# Board1.net
KiCad netlist of a schematic drawn in EAGLE
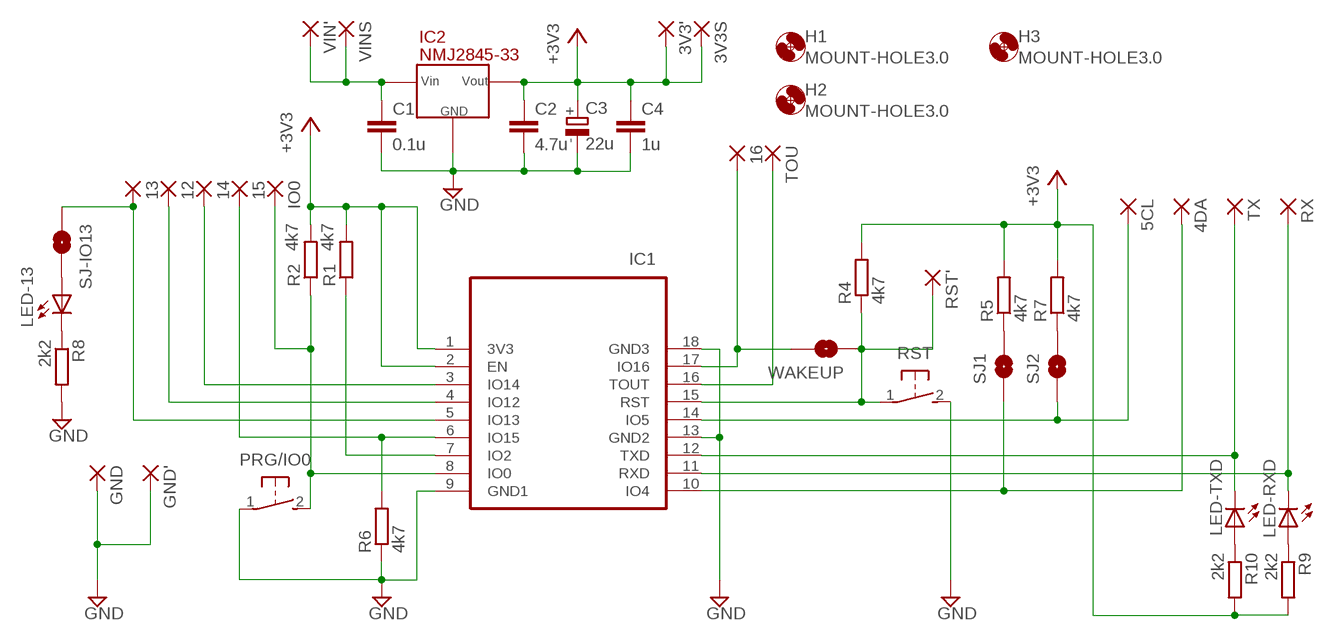
[diagram p0: schematic, sheet 1]

(export (version "E")
  (design (tool "Eeschema 10.0.6"))
  (components
    (comp (ref "3V3'")
      (value "1,6/0,8")
      (footprint "eagle-import:1,6_0,8")
      (libsource (lib "eagle-import") (part "1,6/0,8"))
    )
    (comp (ref "3V3S")
      (value "1,6/0,8")
      (footprint "eagle-import:1,6_0,8")
      (libsource (lib "eagle-import") (part "1,6/0,8"))
    )
    (comp (ref "4DA")
      (value "1,6/0,8")
      (footprint "eagle-import:1,6_0,8")
      (libsource (lib "eagle-import") (part "1,6/0,8"))
    )
    (comp (ref "5CL")
      (value "1,6/0,8")
      (footprint "eagle-import:1,6_0,8")
      (libsource (lib "eagle-import") (part "1,6/0,8"))
    )
    (comp (ref "12")
      (value "1,6/0,8")
      (footprint "eagle-import:1,6_0,8")
      (libsource (lib "eagle-import") (part "1,6/0,8"))
    )
    (comp (ref "13")
      (value "1,6/0,8")
      (footprint "eagle-import:1,6_0,8")
      (libsource (lib "eagle-import") (part "1,6/0,8"))
    )
    (comp (ref "14")
      (value "1,6/0,8")
      (footprint "eagle-import:1,6_0,8")
      (libsource (lib "eagle-import") (part "1,6/0,8"))
    )
    (comp (ref "15")
      (value "1,6/0,8")
      (footprint "eagle-import:1,6_0,8")
      (libsource (lib "eagle-import") (part "1,6/0,8"))
    )
    (comp (ref "16")
      (value "1,6/0,8")
      (footprint "eagle-import:1,6_0,8")
      (libsource (lib "eagle-import") (part "1,6/0,8"))
    )
    (comp (ref "C1")
      (value "0.1u")
      (footprint "eagle-import:C0603")
      (libsource (lib "eagle-import") (part "C-EUC0603"))
    )
    (comp (ref "C2")
      (value "4.7u")
      (footprint "eagle-import:C0805")
      (libsource (lib "eagle-import") (part "resistor_C-EUC0805"))
    )
    (comp (ref "C3")
      (value "22u")
      (footprint "eagle-import:C6")
      (libsource (lib "eagle-import") (part "OS-CON/C6C"))
    )
    (comp (ref "C4")
      (value "1u")
      (footprint "eagle-import:C0603")
      (libsource (lib "eagle-import") (part "C-EUC0603"))
    )
    (comp (ref "GND")
      (value "1,6/0,8")
      (footprint "eagle-import:1,6_0,8")
      (libsource (lib "eagle-import") (part "1,6/0,8"))
    )
    (comp (ref "GND'")
      (value "1,6/0,8")
      (footprint "eagle-import:1,6_0,8")
      (libsource (lib "eagle-import") (part "1,6/0,8"))
    )
    (comp (ref "H1")
      (value "MOUNT-HOLE3.0")
      (footprint "eagle-import:3,0")
      (libsource (lib "eagle-import") (part "MOUNT-HOLE3.0"))
    )
    (comp (ref "H2")
      (value "MOUNT-HOLE3.0")
      (footprint "eagle-import:3,0")
      (libsource (lib "eagle-import") (part "MOUNT-HOLE3.0"))
    )
    (comp (ref "H3")
      (value "MOUNT-HOLE3.0")
      (footprint "eagle-import:3,0")
      (libsource (lib "eagle-import") (part "MOUNT-HOLE3.0"))
    )
    (comp (ref "IC1")
      (value "ESP-WROOM-02FRONT-FACE")
      (footprint "eagle-import:FRONT-FACE")
      (libsource (lib "eagle-import") (part "ESP-WROOM-02FRONT-FACE"))
    )
    (comp (ref "IC2")
      (value "NMJ2845-33")
      (footprint "eagle-import:TO-252-3")
      (libsource (lib "eagle-import") (part "NJM2845DL1"))
    )
    (comp (ref "IO0")
      (value "1,6/0,8")
      (footprint "eagle-import:1,6_0,8")
      (libsource (lib "eagle-import") (part "1,6/0,8"))
    )
    (comp (ref "LED-13")
      (value "IO13")
      (footprint "eagle-import:CHIP-LED0603")
      (libsource (lib "eagle-import") (part "LEDCHIP-LED0603"))
    )
    (comp (ref "LED-RXD")
      (value "R")
      (footprint "eagle-import:CHIP-LED0603")
      (libsource (lib "eagle-import") (part "LEDCHIP-LED0603"))
    )
    (comp (ref "LED-TXD")
      (value "T")
      (footprint "eagle-import:CHIP-LED0603")
      (libsource (lib "eagle-import") (part "LEDCHIP-LED0603"))
    )
    (comp (ref "PRG/IO0")
      (value "SWITCH-TACTILESW")
      (footprint "eagle-import:SWITCH-TACTILE")
      (libsource (lib "eagle-import") (part "SWITCH-TACTILESW"))
    )
    (comp (ref "R1")
      (value "4k7")
      (footprint "eagle-import:R0603")
      (libsource (lib "eagle-import") (part "R-EU_R0603"))
    )
    (comp (ref "R2")
      (value "4k7")
      (footprint "eagle-import:R0603")
      (libsource (lib "eagle-import") (part "R-EU_R0603"))
    )
    (comp (ref "R4")
      (value "4k7")
      (footprint "eagle-import:R0603")
      (libsource (lib "eagle-import") (part "R-EU_R0603"))
    )
    (comp (ref "R5")
      (value "4k7")
      (footprint "eagle-import:R0603")
      (libsource (lib "eagle-import") (part "R-EU_R0603"))
    )
    (comp (ref "R6")
      (value "4k7")
      (footprint "eagle-import:R0603")
      (libsource (lib "eagle-import") (part "R-EU_R0603"))
    )
    (comp (ref "R7")
      (value "4k7")
      (footprint "eagle-import:R0603")
      (libsource (lib "eagle-import") (part "R-EU_R0603"))
    )
    (comp (ref "R8")
      (value "2k2")
      (footprint "eagle-import:R0603")
      (libsource (lib "eagle-import") (part "R-EU_R0603"))
    )
    (comp (ref "R9")
      (value "2k2")
      (footprint "eagle-import:R0603")
      (libsource (lib "eagle-import") (part "R-EU_R0603"))
    )
    (comp (ref "R10")
      (value "2k2")
      (footprint "eagle-import:R0603")
      (libsource (lib "eagle-import") (part "R-EU_R0603"))
    )
    (comp (ref "RST")
      (value "SWITCH-TACTILESW")
      (footprint "eagle-import:SWITCH-TACTILE")
      (libsource (lib "eagle-import") (part "SWITCH-TACTILESW"))
    )
    (comp (ref "RST'")
      (value "1,6/0,8")
      (footprint "eagle-import:1,6_0,8")
      (libsource (lib "eagle-import") (part "1,6/0,8"))
    )
    (comp (ref "RX")
      (value "1,6/0,8")
      (footprint "eagle-import:1,6_0,8")
      (libsource (lib "eagle-import") (part "1,6/0,8"))
    )
    (comp (ref "SJ-IO13")
      (value "SOLDERJUMPERNO")
      (footprint "eagle-import:SJ_2S-NO")
      (libsource (lib "eagle-import") (part "SOLDERJUMPERNO"))
    )
    (comp (ref "SJ1")
      (value "SDA/PU")
      (footprint "eagle-import:SJ_2S-NO")
      (libsource (lib "eagle-import") (part "SOLDERJUMPERNO"))
    )
    (comp (ref "SJ2")
      (value "SCL/PU")
      (footprint "eagle-import:SJ_2S-NO")
      (libsource (lib "eagle-import") (part "SOLDERJUMPERNO"))
    )
    (comp (ref "TOU")
      (value "1,6/0,8")
      (footprint "eagle-import:1,6_0,8")
      (libsource (lib "eagle-import") (part "1,6/0,8"))
    )
    (comp (ref "TX")
      (value "1,6/0,8")
      (footprint "eagle-import:1,6_0,8")
      (libsource (lib "eagle-import") (part "1,6/0,8"))
    )
    (comp (ref "VIN'")
      (value "1,6/0,8")
      (footprint "eagle-import:1,6_0,8")
      (libsource (lib "eagle-import") (part "1,6/0,8"))
    )
    (comp (ref "VINS")
      (value "1,6/0,8")
      (footprint "eagle-import:1,6_0,8")
      (libsource (lib "eagle-import") (part "1,6/0,8"))
    )
    (comp (ref "WAKEUP")
      (value "SOLDERJUMPERNO")
      (footprint "eagle-import:SJ_2S-NO")
      (libsource (lib "eagle-import") (part "SOLDERJUMPERNO"))
    )
  )
  (nets
    (net (code "1") (name "+3V3") (class "Default")
      (node (ref "3V3'") (pin "1") (pinfunction "P_1") (pintype "passive"))
      (node (ref "3V3S") (pin "1") (pinfunction "P_1") (pintype "passive"))
      (node (ref "C2") (pin "1") (pinfunction "1_1") (pintype "passive"))
      (node (ref "C3") (pin "+") (pinfunction "+_+") (pintype "passive"))
      (node (ref "C4") (pin "1") (pinfunction "1_1") (pintype "passive"))
      (node (ref "IC1") (pin "1") (pinfunction "3V3_1") (pintype "power_in"))
      (node (ref "IC1") (pin "2") (pinfunction "EN_2") (pintype "bidirectional"))
      (node (ref "IC2") (pin "VOUT") (pinfunction "VOUT_VOUT") (pintype "power_in"))
      (node (ref "R1") (pin "2") (pinfunction "2_2") (pintype "passive"))
      (node (ref "R10") (pin "2") (pinfunction "2_2") (pintype "passive"))
      (node (ref "R2") (pin "2") (pinfunction "2_2") (pintype "passive"))
      (node (ref "R4") (pin "2") (pinfunction "2_2") (pintype "passive"))
      (node (ref "R5") (pin "2") (pinfunction "2_2") (pintype "passive"))
      (node (ref "R7") (pin "2") (pinfunction "2_2") (pintype "passive"))
      (node (ref "R9") (pin "2") (pinfunction "2_2") (pintype "passive"))
    )
    (net (code "2") (name "GND") (class "Default")
      (node (ref "C1") (pin "2") (pinfunction "2_2") (pintype "passive"))
      (node (ref "C2") (pin "2") (pinfunction "2_2") (pintype "passive"))
      (node (ref "C3") (pin "-") (pinfunction "-_-") (pintype "passive"))
      (node (ref "C4") (pin "2") (pinfunction "2_2") (pintype "passive"))
      (node (ref "GND") (pin "1") (pinfunction "P_1") (pintype "passive"))
      (node (ref "GND'") (pin "1") (pinfunction "P_1") (pintype "passive"))
      (node (ref "IC1") (pin "13") (pinfunction "GND2_13") (pintype "power_in"))
      (node (ref "IC1") (pin "18") (pinfunction "GND3_18") (pintype "power_in"))
      (node (ref "IC1") (pin "9") (pinfunction "GND1_9") (pintype "power_in"))
      (node (ref "IC2") (pin "GND") (pinfunction "GND_GND") (pintype "power_in"))
      (node (ref "PRG/IO0") (pin "1") (pinfunction "1_1") (pintype "passive"))
      (node (ref "R6") (pin "1") (pinfunction "1_1") (pintype "passive"))
      (node (ref "R8") (pin "2") (pinfunction "2_2") (pintype "passive"))
      (node (ref "RST") (pin "2") (pinfunction "2_2") (pintype "passive"))
    )
    (net (code "3") (name "Net-(4DA-P)") (class "Default")
      (node (ref "4DA") (pin "1") (pinfunction "P_1") (pintype "passive"))
      (node (ref "IC1") (pin "10") (pinfunction "IO4_10") (pintype "bidirectional"))
      (node (ref "SJ1") (pin "1") (pinfunction "1_1") (pintype "passive"))
    )
    (net (code "4") (name "Net-(5CL-P)") (class "Default")
      (node (ref "5CL") (pin "1") (pinfunction "P_1") (pintype "passive"))
      (node (ref "IC1") (pin "14") (pinfunction "IO5_14") (pintype "open_collector"))
      (node (ref "SJ2") (pin "1") (pinfunction "1_1") (pintype "passive"))
    )
    (net (code "5") (name "Net-(12-P)") (class "Default")
      (node (ref "12") (pin "1") (pinfunction "P_1") (pintype "passive"))
      (node (ref "IC1") (pin "4") (pinfunction "IO12_4") (pintype "bidirectional"))
    )
    (net (code "6") (name "Net-(13-P)") (class "Default")
      (node (ref "13") (pin "1") (pinfunction "P_1") (pintype "passive"))
      (node (ref "IC1") (pin "5") (pinfunction "IO13_5") (pintype "bidirectional"))
      (node (ref "SJ-IO13") (pin "1") (pinfunction "1_1") (pintype "passive"))
    )
    (net (code "7") (name "Net-(14-P)") (class "Default")
      (node (ref "14") (pin "1") (pinfunction "P_1") (pintype "passive"))
      (node (ref "IC1") (pin "3") (pinfunction "IO14_3") (pintype "bidirectional"))
    )
    (net (code "8") (name "Net-(15-P)") (class "Default")
      (node (ref "15") (pin "1") (pinfunction "P_1") (pintype "passive"))
      (node (ref "IC1") (pin "6") (pinfunction "IO15_6") (pintype "bidirectional"))
      (node (ref "R6") (pin "2") (pinfunction "2_2") (pintype "passive"))
    )
    (net (code "9") (name "Net-(16-P)") (class "Default")
      (node (ref "16") (pin "1") (pinfunction "P_1") (pintype "passive"))
      (node (ref "IC1") (pin "17") (pinfunction "IO16_17") (pintype "bidirectional"))
      (node (ref "WAKEUP") (pin "2") (pinfunction "2_2") (pintype "passive"))
    )
    (net (code "10") (name "Net-(IC1-IO0)") (class "Default")
      (node (ref "IC1") (pin "8") (pinfunction "IO0_8") (pintype "bidirectional"))
      (node (ref "IO0") (pin "1") (pinfunction "P_1") (pintype "passive"))
      (node (ref "PRG/IO0") (pin "2") (pinfunction "2_2") (pintype "passive"))
      (node (ref "R2") (pin "1") (pinfunction "1_1") (pintype "passive"))
    )
    (net (code "11") (name "Net-(IC1-IO2)") (class "Default")
      (node (ref "IC1") (pin "7") (pinfunction "IO2_7") (pintype "bidirectional"))
      (node (ref "R1") (pin "1") (pinfunction "1_1") (pintype "passive"))
    )
    (net (code "12") (name "Net-(IC1-RST)") (class "Default")
      (node (ref "IC1") (pin "15") (pinfunction "RST_15") (pintype "bidirectional"))
      (node (ref "R4") (pin "1") (pinfunction "1_1") (pintype "passive"))
      (node (ref "RST") (pin "1") (pinfunction "1_1") (pintype "passive"))
      (node (ref "RST'") (pin "1") (pinfunction "P_1") (pintype "passive"))
      (node (ref "WAKEUP") (pin "1") (pinfunction "1_1") (pintype "passive"))
    )
    (net (code "13") (name "Net-(IC1-RXD)") (class "Default")
      (node (ref "IC1") (pin "11") (pinfunction "RXD_11") (pintype "bidirectional"))
      (node (ref "LED-RXD") (pin "C") (pinfunction "C_C") (pintype "passive"))
      (node (ref "RX") (pin "1") (pinfunction "P_1") (pintype "passive"))
    )
    (net (code "14") (name "Net-(IC1-TOUT)") (class "Default")
      (node (ref "IC1") (pin "16") (pinfunction "TOUT_16") (pintype "bidirectional"))
      (node (ref "TOU") (pin "1") (pinfunction "P_1") (pintype "passive"))
    )
    (net (code "15") (name "Net-(IC1-TXD)") (class "Default")
      (node (ref "IC1") (pin "12") (pinfunction "TXD_12") (pintype "bidirectional"))
      (node (ref "LED-TXD") (pin "C") (pinfunction "C_C") (pintype "passive"))
      (node (ref "TX") (pin "1") (pinfunction "P_1") (pintype "passive"))
    )
    (net (code "16") (name "Net-(LED-13-PadA)") (class "Default")
      (node (ref "LED-13") (pin "A") (pinfunction "A_A") (pintype "passive"))
      (node (ref "SJ-IO13") (pin "2") (pinfunction "2_2") (pintype "passive"))
    )
    (net (code "17") (name "Net-(LED-13-PadC)") (class "Default")
      (node (ref "LED-13") (pin "C") (pinfunction "C_C") (pintype "passive"))
      (node (ref "R8") (pin "1") (pinfunction "1_1") (pintype "passive"))
    )
    (net (code "18") (name "Net-(LED-RXD-PadA)") (class "Default")
      (node (ref "LED-RXD") (pin "A") (pinfunction "A_A") (pintype "passive"))
      (node (ref "R9") (pin "1") (pinfunction "1_1") (pintype "passive"))
    )
    (net (code "19") (name "Net-(LED-TXD-PadA)") (class "Default")
      (node (ref "LED-TXD") (pin "A") (pinfunction "A_A") (pintype "passive"))
      (node (ref "R10") (pin "1") (pinfunction "1_1") (pintype "passive"))
    )
    (net (code "20") (name "Net-(R5-Pad1)") (class "Default")
      (node (ref "R5") (pin "1") (pinfunction "1_1") (pintype "passive"))
      (node (ref "SJ1") (pin "2") (pinfunction "2_2") (pintype "passive"))
    )
    (net (code "21") (name "Net-(R7-Pad1)") (class "Default")
      (node (ref "R7") (pin "1") (pinfunction "1_1") (pintype "passive"))
      (node (ref "SJ2") (pin "2") (pinfunction "2_2") (pintype "passive"))
    )
    (net (code "22") (name "Net-(VIN'-P)") (class "Default")
      (node (ref "C1") (pin "1") (pinfunction "1_1") (pintype "passive"))
      (node (ref "IC2") (pin "VIN") (pinfunction "VIN_VIN") (pintype "power_in"))
      (node (ref "VIN'") (pin "1") (pinfunction "P_1") (pintype "passive"))
      (node (ref "VINS") (pin "1") (pinfunction "P_1") (pintype "passive"))
    )
  )
)
